# PWM_v1_0.net
KiCad netlist of a schematic drawn in EAGLE
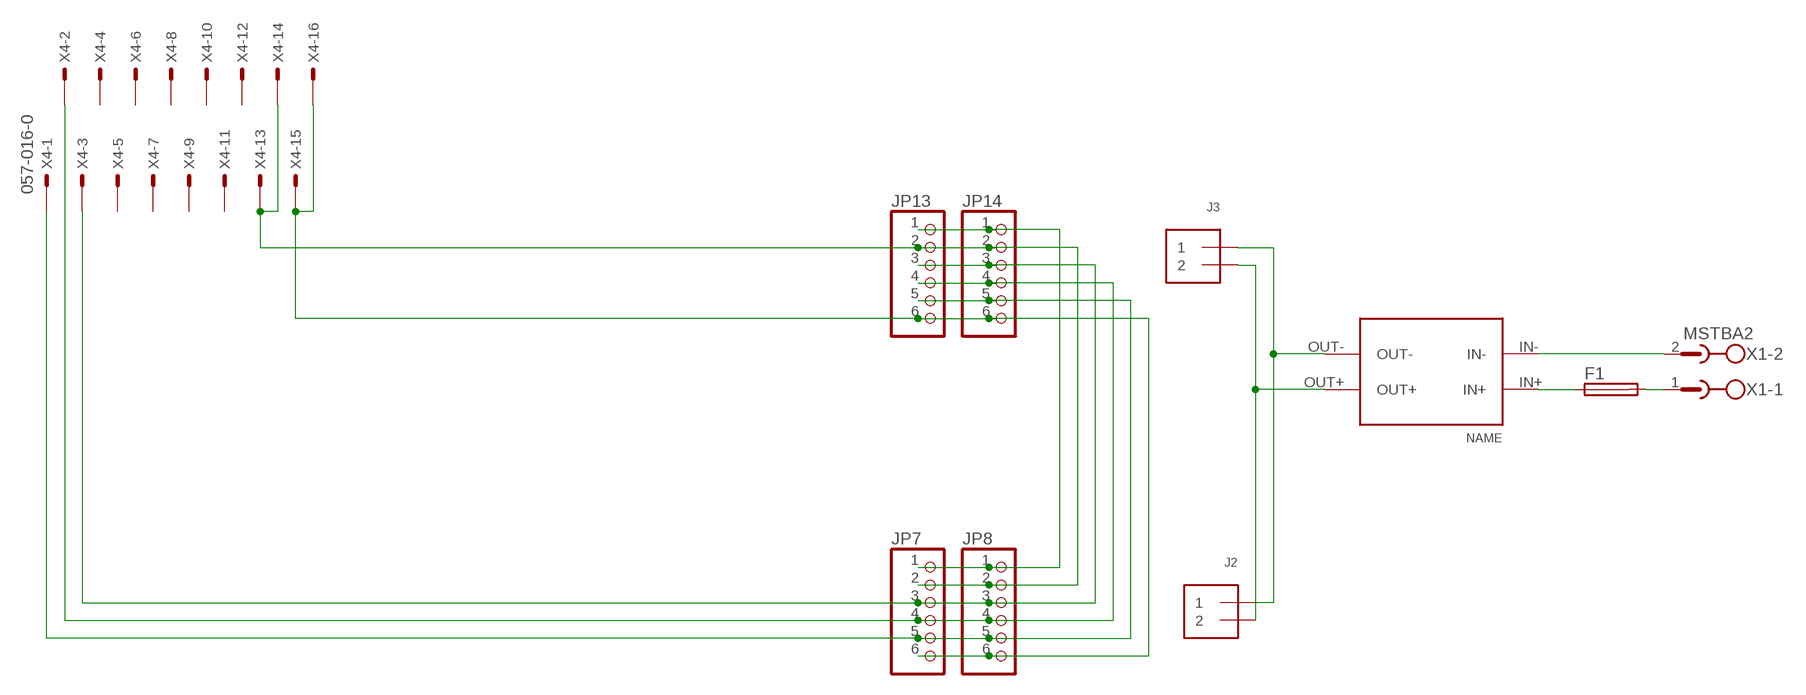
[diagram p0: schematic, sheet 1]

(export (version "E")
  (design (tool "Eeschema 10.0.6"))
  (components
    (comp (ref "F1")
      (value "SH25")
      (footprint "eagle-import:SH25")
      (fields (field (name "MF") "SCHURTER") (field (name "MPN") "0031.8211"))
      (libsource (lib "eagle-import") (part "SH25"))
    )
    (comp (ref "J2")
      (value "TERMBLOCK_1X2")
      (footprint "eagle-import:TERMBLOCK_1X2-3.5MM")
      (libsource (lib "eagle-import") (part "TERMBLOCK_1X2"))
    )
    (comp (ref "J3")
      (value "TERMBLOCK_1X2")
      (footprint "eagle-import:TERMBLOCK_1X2-3.5MM")
      (libsource (lib "eagle-import") (part "TERMBLOCK_1X2"))
    )
    (comp (ref "JP7")
      (value "PINHD-1X6CB")
      (footprint "eagle-import:1X06-CLEANBIG")
      (libsource (lib "eagle-import") (part "PINHD-1X6CB"))
    )
    (comp (ref "JP8")
      (value "PINHD-1X6CB")
      (footprint "eagle-import:1X06-CLEANBIG")
      (libsource (lib "eagle-import") (part "PINHD-1X6CB"))
    )
    (comp (ref "JP13")
      (value "PINHD-1X6CB")
      (footprint "eagle-import:1X06-CLEANBIG")
      (libsource (lib "eagle-import") (part "PINHD-1X6CB"))
    )
    (comp (ref "JP14")
      (value "PINHD-1X6CB")
      (footprint "eagle-import:1X06-CLEANBIG")
      (libsource (lib "eagle-import") (part "PINHD-1X6CB"))
    )
    (comp (ref "U$2")
      (value "CP8-ADJ")
      (footprint "eagle-import:CP8-ADJ")
      (libsource (lib "eagle-import") (part "CP8-ADJ"))
    )
    (comp (ref "X1")
      (value "MSTBA2")
      (footprint "eagle-import:MSTBA2")
      (fields (field (name "MF") "FARNELL") (field (name "MPN") "1757242"))
      (libsource (lib "eagle-import") (part "MSTBA2"))
    )
    (comp (ref "X4")
      (value "057-016-0")
      (footprint "eagle-import:057-016-0")
      (libsource (lib "eagle-import") (part "057-016-0"))
    )
  )
  (nets
    (net (code "1") (name "Net-(F1-Pad1)") (class "Default")
      (node (ref "F1") (pin "1") (pinfunction "1_1") (pintype "passive"))
      (node (ref "U$2") (pin "IN+") (pinfunction "IN+_IN+") (pintype "passive"))
    )
    (net (code "2") (name "Net-(F1-Pad2)") (class "Default")
      (node (ref "F1") (pin "2") (pinfunction "2_2") (pintype "passive"))
      (node (ref "X1") (pin "1") (pinfunction "1_1") (pintype "passive"))
    )
    (net (code "3") (name "Net-(J2-Pad1)") (class "Default")
      (node (ref "J2") (pin "1") (pinfunction "1_1") (pintype "passive"))
      (node (ref "J3") (pin "1") (pinfunction "1_1") (pintype "passive"))
      (node (ref "U$2") (pin "OUT-") (pinfunction "OUT-_OUT-") (pintype "passive"))
    )
    (net (code "4") (name "Net-(J2-Pad2)") (class "Default")
      (node (ref "J2") (pin "2") (pinfunction "2_2") (pintype "passive"))
      (node (ref "J3") (pin "2") (pinfunction "2_2") (pintype "passive"))
      (node (ref "U$2") (pin "OUT+") (pinfunction "OUT+_OUT+") (pintype "passive"))
    )
    (net (code "5") (name "Net-(JP13-Pad1)") (class "Default")
      (node (ref "JP13") (pin "1") (pinfunction "1_1") (pintype "passive"))
      (node (ref "JP14") (pin "1") (pinfunction "1_1") (pintype "passive"))
      (node (ref "JP7") (pin "1") (pinfunction "1_1") (pintype "passive"))
      (node (ref "JP8") (pin "1") (pinfunction "1_1") (pintype "passive"))
    )
    (net (code "6") (name "Net-(X1B-1)") (class "Default")
      (node (ref "U$2") (pin "IN-") (pinfunction "IN-_IN-") (pintype "passive"))
      (node (ref "X1") (pin "2") (pinfunction "1_2") (pintype "passive"))
    )
    (net (code "7") (name "Net-(X4A-S)") (class "Default")
      (node (ref "JP13") (pin "5") (pinfunction "5_5") (pintype "passive"))
      (node (ref "JP14") (pin "5") (pinfunction "5_5") (pintype "passive"))
      (node (ref "JP7") (pin "5") (pinfunction "5_5") (pintype "passive"))
      (node (ref "JP8") (pin "5") (pinfunction "5_5") (pintype "passive"))
      (node (ref "X4") (pin "1") (pinfunction "S_1") (pintype "passive"))
    )
    (net (code "8") (name "Net-(X4E-S)") (class "Default")
      (node (ref "JP13") (pin "2") (pinfunction "2_2") (pintype "passive"))
      (node (ref "JP14") (pin "2") (pinfunction "2_2") (pintype "passive"))
      (node (ref "JP7") (pin "2") (pinfunction "2_2") (pintype "passive"))
      (node (ref "JP8") (pin "2") (pinfunction "2_2") (pintype "passive"))
      (node (ref "X4") (pin "13") (pinfunction "S_13") (pintype "passive"))
      (node (ref "X4") (pin "14") (pinfunction "S_14") (pintype "passive"))
    )
    (net (code "9") (name "Net-(X4G-S)") (class "Default")
      (node (ref "JP13") (pin "6") (pinfunction "6_6") (pintype "passive"))
      (node (ref "JP14") (pin "6") (pinfunction "6_6") (pintype "passive"))
      (node (ref "JP7") (pin "6") (pinfunction "6_6") (pintype "passive"))
      (node (ref "JP8") (pin "6") (pinfunction "6_6") (pintype "passive"))
      (node (ref "X4") (pin "15") (pinfunction "S_15") (pintype "passive"))
      (node (ref "X4") (pin "16") (pinfunction "S_16") (pintype "passive"))
    )
    (net (code "10") (name "Net-(X4I-S)") (class "Default")
      (node (ref "JP13") (pin "4") (pinfunction "4_4") (pintype "passive"))
      (node (ref "JP14") (pin "4") (pinfunction "4_4") (pintype "passive"))
      (node (ref "JP7") (pin "4") (pinfunction "4_4") (pintype "passive"))
      (node (ref "JP8") (pin "4") (pinfunction "4_4") (pintype "passive"))
      (node (ref "X4") (pin "2") (pinfunction "S_2") (pintype "passive"))
    )
    (net (code "11") (name "Net-(X4J-S)") (class "Default")
      (node (ref "JP13") (pin "3") (pinfunction "3_3") (pintype "passive"))
      (node (ref "JP14") (pin "3") (pinfunction "3_3") (pintype "passive"))
      (node (ref "JP7") (pin "3") (pinfunction "3_3") (pintype "passive"))
      (node (ref "JP8") (pin "3") (pinfunction "3_3") (pintype "passive"))
      (node (ref "X4") (pin "3") (pinfunction "S_3") (pintype "passive"))
    )
    (net (code "12") (name "unconnected-(X4B-S-Pad10)") (class "Default")
      (node (ref "X4") (pin "10") (pinfunction "S_10") (pintype "passive"))
    )
    (net (code "13") (name "unconnected-(X4C-S-Pad11)") (class "Default")
      (node (ref "X4") (pin "11") (pinfunction "S_11") (pintype "passive"))
    )
    (net (code "14") (name "unconnected-(X4D-S-Pad12)") (class "Default")
      (node (ref "X4") (pin "12") (pinfunction "S_12") (pintype "passive"))
    )
    (net (code "15") (name "unconnected-(X4K-S-Pad4)") (class "Default")
      (node (ref "X4") (pin "4") (pinfunction "S_4") (pintype "passive"))
    )
    (net (code "16") (name "unconnected-(X4L-S-Pad5)") (class "Default")
      (node (ref "X4") (pin "5") (pinfunction "S_5") (pintype "passive"))
    )
    (net (code "17") (name "unconnected-(X4M-S-Pad6)") (class "Default")
      (node (ref "X4") (pin "6") (pinfunction "S_6") (pintype "passive"))
    )
    (net (code "18") (name "unconnected-(X4N-S-Pad7)") (class "Default")
      (node (ref "X4") (pin "7") (pinfunction "S_7") (pintype "passive"))
    )
    (net (code "19") (name "unconnected-(X4O-S-Pad8)") (class "Default")
      (node (ref "X4") (pin "8") (pinfunction "S_8") (pintype "passive"))
    )
    (net (code "20") (name "unconnected-(X4P-S-Pad9)") (class "Default")
      (node (ref "X4") (pin "9") (pinfunction "S_9") (pintype "passive"))
    )
  )
)
